# front_board.net
KiCad netlist of a schematic drawn in EAGLE
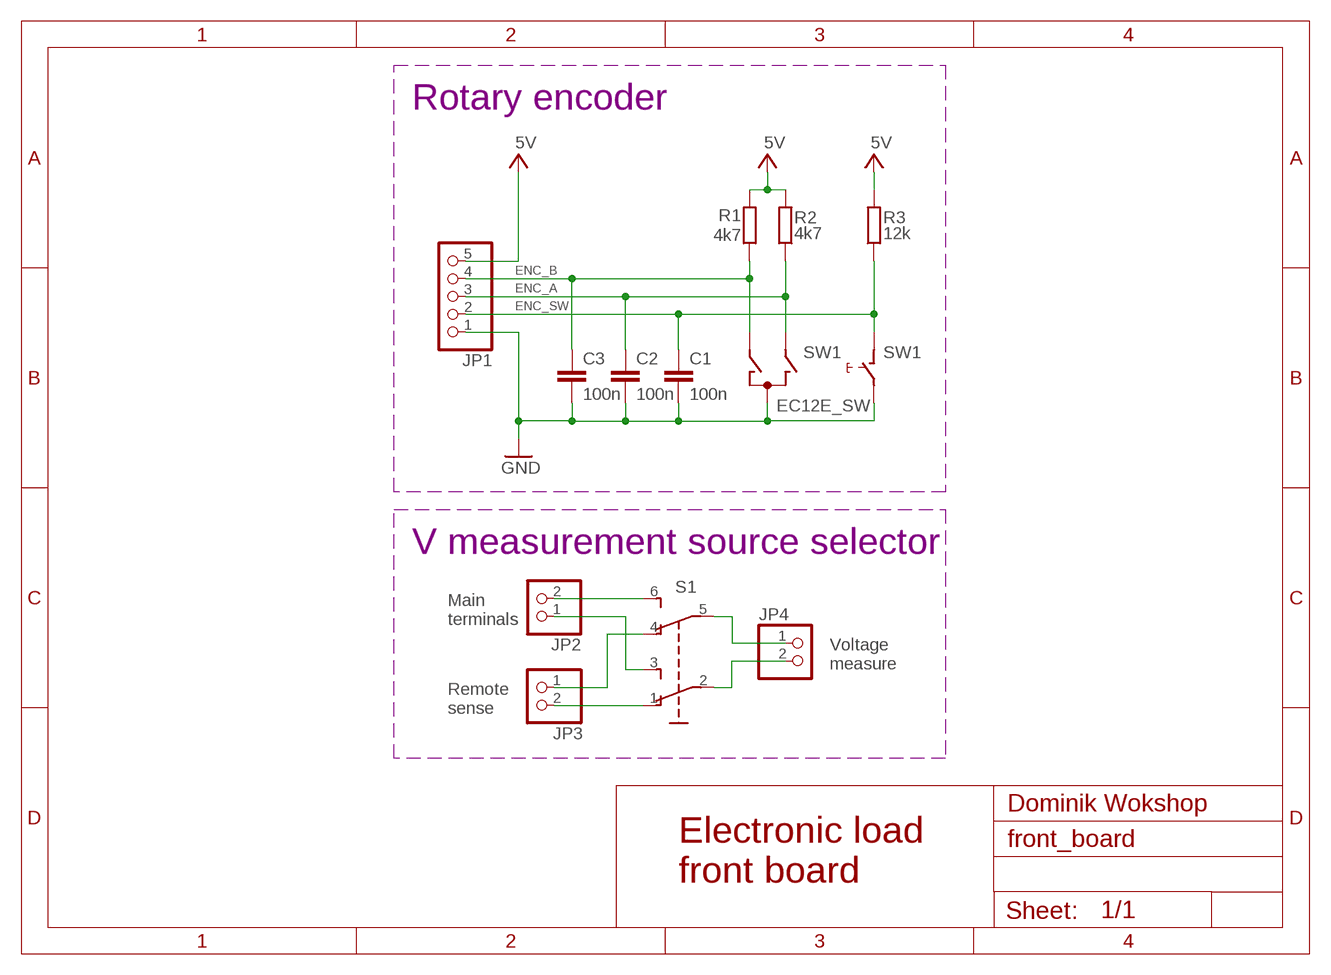
[diagram p0: schematic, sheet 1]

(export (version "E")
  (design (tool "Eeschema 10.0.6"))
  (components
    (comp (ref "C1")
      (value "100n")
      (footprint "eagle-import:C0603")
      (libsource (lib "eagle-import") (part "C-EUC0603"))
    )
    (comp (ref "C2")
      (value "100n")
      (footprint "eagle-import:C0603")
      (libsource (lib "eagle-import") (part "C-EUC0603"))
    )
    (comp (ref "C3")
      (value "100n")
      (footprint "eagle-import:C0603")
      (libsource (lib "eagle-import") (part "C-EUC0603"))
    )
    (comp (ref "JP1")
      (value "PINHD-1X5/90")
      (footprint "eagle-import:1X05_90")
      (libsource (lib "eagle-import") (part "PINHD-1X5/90"))
    )
    (comp (ref "JP2")
      (value "PINHD-1X2/90")
      (footprint "eagle-import:1X02_90")
      (libsource (lib "eagle-import") (part "PINHD-1X2/90"))
    )
    (comp (ref "JP3")
      (value "PINHD-1X2/90")
      (footprint "eagle-import:1X02_90")
      (libsource (lib "eagle-import") (part "PINHD-1X2/90"))
    )
    (comp (ref "JP4")
      (value "PINHD-1X2/90")
      (footprint "eagle-import:1X02_90")
      (libsource (lib "eagle-import") (part "PINHD-1X2/90"))
    )
    (comp (ref "R1")
      (value "4k7")
      (footprint "eagle-import:R0603")
      (libsource (lib "eagle-import") (part "R-EU_R0603"))
    )
    (comp (ref "R2")
      (value "4k7")
      (footprint "eagle-import:R0603")
      (libsource (lib "eagle-import") (part "R-EU_R0603"))
    )
    (comp (ref "R3")
      (value "12k")
      (footprint "eagle-import:R0603")
      (libsource (lib "eagle-import") (part "R-EU_R0603"))
    )
    (comp (ref "S1")
      (value "TL46PO")
      (footprint "eagle-import:TL4XPO")
      (libsource (lib "eagle-import") (part "TL46PO"))
    )
    (comp (ref "SW1")
      (value "EC12E_SW")
      (footprint "eagle-import:ALPS_EC12E_SW")
      (fields (field (name "MPN") "EC12E2424407"))
      (libsource (lib "eagle-import") (part "EC12E_SW"))
    )
  )
  (nets
    (net (code "1") (name "/ENC_A") (class "Default")
      (node (ref "C2") (pin "1") (pinfunction "1_1") (pintype "passive"))
      (node (ref "JP1") (pin "3") (pinfunction "3_3") (pintype "passive"))
      (node (ref "R2") (pin "1") (pinfunction "1_1") (pintype "passive"))
      (node (ref "SW1") (pin "B") (pinfunction "B_B") (pintype "passive"))
    )
    (net (code "2") (name "/ENC_B") (class "Default")
      (node (ref "C3") (pin "1") (pinfunction "1_1") (pintype "passive"))
      (node (ref "JP1") (pin "4") (pinfunction "4_4") (pintype "passive"))
      (node (ref "R1") (pin "1") (pinfunction "1_1") (pintype "passive"))
      (node (ref "SW1") (pin "A") (pinfunction "A_A") (pintype "passive"))
    )
    (net (code "3") (name "/ENC_SW") (class "Default")
      (node (ref "C1") (pin "1") (pinfunction "1_1") (pintype "passive"))
      (node (ref "JP1") (pin "2") (pinfunction "2_2") (pintype "passive"))
      (node (ref "R3") (pin "1") (pinfunction "1_1") (pintype "passive"))
      (node (ref "SW1") (pin "D") (pinfunction "1_D") (pintype "passive"))
    )
    (net (code "4") (name "GND") (class "Default")
      (node (ref "C1") (pin "2") (pinfunction "2_2") (pintype "passive"))
      (node (ref "C2") (pin "2") (pinfunction "2_2") (pintype "passive"))
      (node (ref "C3") (pin "2") (pinfunction "2_2") (pintype "passive"))
      (node (ref "JP1") (pin "1") (pinfunction "1_1") (pintype "passive"))
      (node (ref "SW1") (pin "C") (pinfunction "C_C") (pintype "passive"))
      (node (ref "SW1") (pin "E") (pinfunction "2_E") (pintype "passive"))
    )
    (net (code "5") (name "Net-(S1-O)") (class "Default")
      (node (ref "JP3") (pin "2") (pinfunction "2_2") (pintype "passive"))
      (node (ref "S1") (pin "1") (pinfunction "O_1") (pintype "passive"))
    )
    (net (code "6") (name "Net-(S1-O1)") (class "Default")
      (node (ref "JP3") (pin "1") (pinfunction "1_1") (pintype "passive"))
      (node (ref "S1") (pin "4") (pinfunction "O1_4") (pintype "passive"))
    )
    (net (code "7") (name "Net-(S1-P)") (class "Default")
      (node (ref "JP4") (pin "2") (pinfunction "2_2") (pintype "passive"))
      (node (ref "S1") (pin "2") (pinfunction "P_2") (pintype "passive"))
    )
    (net (code "8") (name "Net-(S1-P1)") (class "Default")
      (node (ref "JP4") (pin "1") (pinfunction "1_1") (pintype "passive"))
      (node (ref "S1") (pin "5") (pinfunction "P1_5") (pintype "passive"))
    )
    (net (code "9") (name "Net-(S1-S)") (class "Default")
      (node (ref "JP2") (pin "1") (pinfunction "1_1") (pintype "passive"))
      (node (ref "S1") (pin "3") (pinfunction "S_3") (pintype "passive"))
    )
    (net (code "10") (name "Net-(S1-S1)") (class "Default")
      (node (ref "JP2") (pin "2") (pinfunction "2_2") (pintype "passive"))
      (node (ref "S1") (pin "6") (pinfunction "S1_6") (pintype "passive"))
    )
    (net (code "11") (name "VCC") (class "Default")
      (node (ref "JP1") (pin "5") (pinfunction "5_5") (pintype "passive"))
      (node (ref "R1") (pin "2") (pinfunction "2_2") (pintype "passive"))
      (node (ref "R2") (pin "2") (pinfunction "2_2") (pintype "passive"))
      (node (ref "R3") (pin "2") (pinfunction "2_2") (pintype "passive"))
    )
  )
)
